# CPLD.net
KiCad netlist of a schematic drawn in Altium Designer
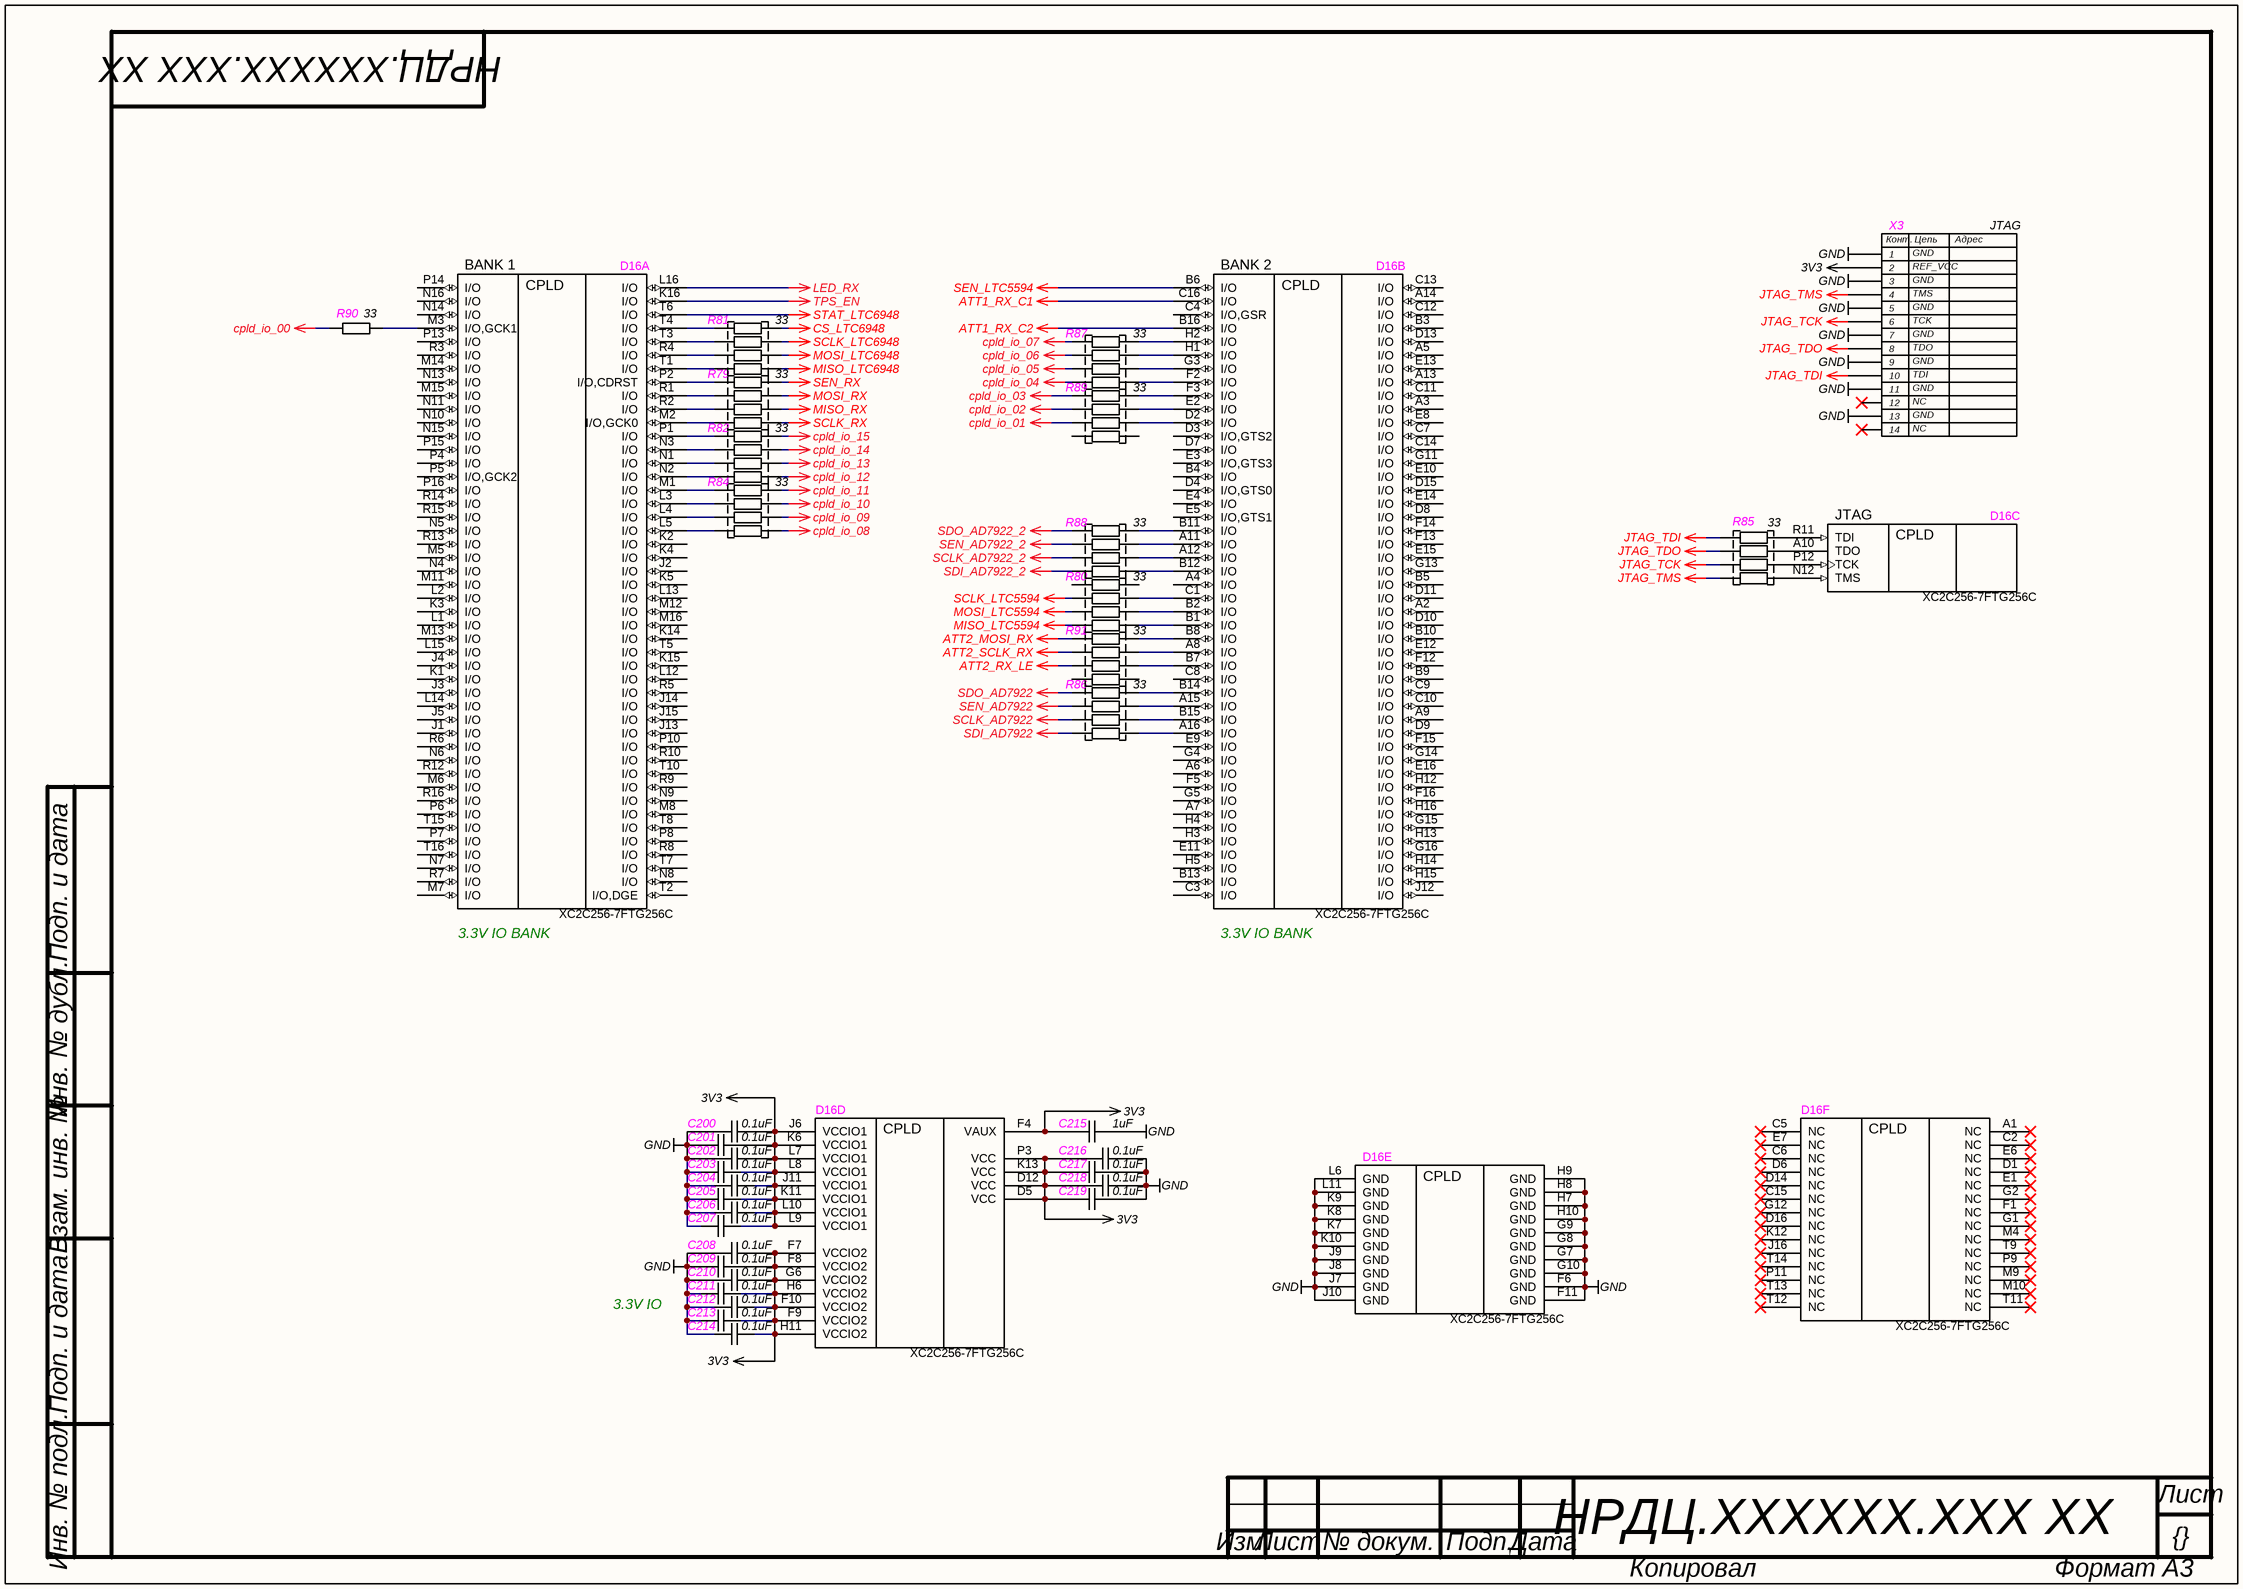
[diagram p0: CPLD.SchDoc]

(export (version "E")
  (design (tool "Eeschema 10.0.6"))
  (components
    (comp (ref "C200")
      (value "0.1uF")
      (footprint "C0402")
      (description "SMD Capacitor")
      (fields (field (name "MANUFACTURER") "Murata") (field (name "TOLERANCE") "10%"))
      (libsource (lib "Kintex_SDR") (part "CAP"))
    )
    (comp (ref "C201")
      (value "0.1uF")
      (footprint "C0402")
      (description "SMD Capacitor")
      (fields (field (name "MANUFACTURER") "Murata") (field (name "TOLERANCE") "10%"))
      (libsource (lib "Kintex_SDR") (part "CAP"))
    )
    (comp (ref "C202")
      (value "0.1uF")
      (footprint "C0402")
      (description "SMD Capacitor")
      (fields (field (name "MANUFACTURER") "Murata") (field (name "TOLERANCE") "10%"))
      (libsource (lib "Kintex_SDR") (part "CAP"))
    )
    (comp (ref "C203")
      (value "0.1uF")
      (footprint "C0402")
      (description "SMD Capacitor")
      (fields (field (name "MANUFACTURER") "Murata") (field (name "TOLERANCE") "10%"))
      (libsource (lib "Kintex_SDR") (part "CAP"))
    )
    (comp (ref "C204")
      (value "0.1uF")
      (footprint "C0402")
      (description "SMD Capacitor")
      (fields (field (name "MANUFACTURER") "Murata") (field (name "TOLERANCE") "10%"))
      (libsource (lib "Kintex_SDR") (part "CAP"))
    )
    (comp (ref "C205")
      (value "0.1uF")
      (footprint "C0402")
      (description "SMD Capacitor")
      (fields (field (name "MANUFACTURER") "Murata") (field (name "TOLERANCE") "10%"))
      (libsource (lib "Kintex_SDR") (part "CAP"))
    )
    (comp (ref "C206")
      (value "0.1uF")
      (footprint "C0402")
      (description "SMD Capacitor")
      (fields (field (name "MANUFACTURER") "Murata") (field (name "TOLERANCE") "10%"))
      (libsource (lib "Kintex_SDR") (part "CAP"))
    )
    (comp (ref "C207")
      (value "0.1uF")
      (footprint "C0402")
      (description "SMD Capacitor")
      (fields (field (name "MANUFACTURER") "Murata") (field (name "TOLERANCE") "10%"))
      (libsource (lib "Kintex_SDR") (part "CAP"))
    )
    (comp (ref "C208")
      (value "0.1uF")
      (footprint "C0402")
      (description "SMD Capacitor")
      (fields (field (name "MANUFACTURER") "Murata") (field (name "TOLERANCE") "10%"))
      (libsource (lib "Kintex_SDR") (part "CAP"))
    )
    (comp (ref "C209")
      (value "0.1uF")
      (footprint "C0402")
      (description "SMD Capacitor")
      (fields (field (name "MANUFACTURER") "Murata") (field (name "TOLERANCE") "10%"))
      (libsource (lib "Kintex_SDR") (part "CAP"))
    )
    (comp (ref "C210")
      (value "0.1uF")
      (footprint "C0402")
      (description "SMD Capacitor")
      (fields (field (name "MANUFACTURER") "Murata") (field (name "TOLERANCE") "10%"))
      (libsource (lib "Kintex_SDR") (part "CAP"))
    )
    (comp (ref "C211")
      (value "0.1uF")
      (footprint "C0402")
      (description "SMD Capacitor")
      (fields (field (name "MANUFACTURER") "Murata") (field (name "TOLERANCE") "10%"))
      (libsource (lib "Kintex_SDR") (part "CAP"))
    )
    (comp (ref "C212")
      (value "0.1uF")
      (footprint "C0402")
      (description "SMD Capacitor")
      (fields (field (name "MANUFACTURER") "Murata") (field (name "TOLERANCE") "10%"))
      (libsource (lib "Kintex_SDR") (part "CAP"))
    )
    (comp (ref "C213")
      (value "0.1uF")
      (footprint "C0402")
      (description "SMD Capacitor")
      (fields (field (name "MANUFACTURER") "Murata") (field (name "TOLERANCE") "10%"))
      (libsource (lib "Kintex_SDR") (part "CAP"))
    )
    (comp (ref "C214")
      (value "0.1uF")
      (footprint "C0402")
      (description "SMD Capacitor")
      (fields (field (name "MANUFACTURER") "Murata") (field (name "TOLERANCE") "10%"))
      (libsource (lib "Kintex_SDR") (part "CAP"))
    )
    (comp (ref "C215")
      (value "1uF")
      (footprint "C0402")
      (description "SMD Capacitor")
      (fields (field (name "MANUFACTURER") "Murata") (field (name "TOLERANCE") "10%"))
      (libsource (lib "Kintex_SDR") (part "CAP"))
    )
    (comp (ref "C216")
      (value "0.1uF")
      (footprint "C0402")
      (description "SMD Capacitor")
      (fields (field (name "MANUFACTURER") "Murata") (field (name "TOLERANCE") "10%"))
      (libsource (lib "Kintex_SDR") (part "CAP"))
    )
    (comp (ref "C217")
      (value "0.1uF")
      (footprint "C0402")
      (description "SMD Capacitor")
      (fields (field (name "MANUFACTURER") "Murata") (field (name "TOLERANCE") "10%"))
      (libsource (lib "Kintex_SDR") (part "CAP"))
    )
    (comp (ref "C218")
      (value "0.1uF")
      (footprint "C0402")
      (description "SMD Capacitor")
      (fields (field (name "MANUFACTURER") "Murata") (field (name "TOLERANCE") "10%"))
      (libsource (lib "Kintex_SDR") (part "CAP"))
    )
    (comp (ref "C219")
      (value "0.1uF")
      (footprint "C0402")
      (description "SMD Capacitor")
      (fields (field (name "MANUFACTURER") "Murata") (field (name "TOLERANCE") "10%"))
      (libsource (lib "Kintex_SDR") (part "CAP"))
    )
    (comp (ref "D16")
      (value "XC2C256-7FTG256C")
      (footprint "DBLib:FTG256")
      (description "CoolRunner-II 1.8V, 256 Macrocell CPLD, 184 User I/Os, 256-Ball FTBGA, Commercial Grade, Pb-Free")
      (libsource (lib "") (part "XC2C256-7FTG256C_2"))
    )
    (comp (ref "R79")
      (value "33")
      (footprint "EXN8V")
      (description "Chip Resistor Array")
      (fields (field (name "TOLERANCE") "5%") (field (name "MANUFACTURER") "Panasonic"))
      (libsource (lib "") (part "RES 4x0402_5"))
    )
    (comp (ref "R80")
      (value "33")
      (footprint "EXN8V")
      (description "Chip Resistor Array")
      (fields (field (name "TOLERANCE") "5%") (field (name "MANUFACTURER") "Panasonic"))
      (libsource (lib "Kintex_SDR") (part "RES 4x0402"))
    )
    (comp (ref "R81")
      (value "33")
      (footprint "EXN8V")
      (description "Chip Resistor Array")
      (fields (field (name "TOLERANCE") "5%") (field (name "MANUFACTURER") "Panasonic"))
      (libsource (lib "") (part "RES 4x0402_1"))
    )
    (comp (ref "R82")
      (value "33")
      (footprint "EXN8V")
      (description "Chip Resistor Array")
      (fields (field (name "TOLERANCE") "5%") (field (name "MANUFACTURER") "Panasonic"))
      (libsource (lib "") (part "RES 4x0402_3"))
    )
    (comp (ref "R84")
      (value "33")
      (footprint "EXN8V")
      (description "Chip Resistor Array")
      (fields (field (name "TOLERANCE") "5%") (field (name "MANUFACTURER") "Panasonic"))
      (libsource (lib "") (part "RES 4x0402_3"))
    )
    (comp (ref "R85")
      (value "33")
      (footprint "EXN8V")
      (description "Chip Resistor Array")
      (fields (field (name "TOLERANCE") "5%") (field (name "MANUFACTURER") "Panasonic"))
      (libsource (lib "Kintex_SDR") (part "RES 4x0402"))
    )
    (comp (ref "R86")
      (value "33")
      (footprint "EXN8V")
      (description "Chip Resistor Array")
      (fields (field (name "TOLERANCE") "5%") (field (name "MANUFACTURER") "Panasonic"))
      (libsource (lib "") (part "RES 4x0402_5"))
    )
    (comp (ref "R87")
      (value "33")
      (footprint "EXN8V")
      (description "Chip Resistor Array")
      (fields (field (name "TOLERANCE") "5%") (field (name "MANUFACTURER") "Panasonic"))
      (libsource (lib "Kintex_SDR") (part "RES 4x0402"))
    )
    (comp (ref "R88")
      (value "33")
      (footprint "EXN8V")
      (description "Chip Resistor Array")
      (fields (field (name "TOLERANCE") "5%") (field (name "MANUFACTURER") "Panasonic"))
      (libsource (lib "") (part "RES 4x0402_2"))
    )
    (comp (ref "R89")
      (value "33")
      (footprint "EXN8V")
      (description "Chip Resistor Array")
      (fields (field (name "TOLERANCE") "5%") (field (name "MANUFACTURER") "Panasonic"))
      (libsource (lib "Kintex_SDR") (part "RES 4x0402"))
    )
    (comp (ref "R90")
      (value "33")
      (footprint "R0402")
      (description "SMD Resistor")
      (fields (field (name "POWER") "0.1 Wt") (field (name "TOLERANCE") "1%"))
      (libsource (lib "Kintex_SDR") (part "RES"))
    )
    (comp (ref "R91")
      (value "33")
      (footprint "EXN8V")
      (description "Chip Resistor Array")
      (fields (field (name "TOLERANCE") "5%") (field (name "MANUFACTURER") "Panasonic"))
      (libsource (lib "") (part "RES 4x0402_4"))
    )
    (comp (ref "X3")
      (value "JTAG")
      (footprint "DBLib:JTAG Mail 2mm")
      (description "2.00mm Pitch, Milli-Grid PCB Header, Dual Row, Vertical, Through Hole, Shrouded, 14\r\nCircuits")
      (fields (field (name "MANUFACTURER") "Molex"))
      (libsource (lib "DBLib") (part "HDR Debug_14-pin"))
    )
  )
  (nets
    (net (code "1") (name "3V3") (class "Default")
      (node (ref "C200") (pin "2") (pinfunction "2_2") (pintype "passive"))
      (node (ref "C201") (pin "2") (pinfunction "2_2") (pintype "passive"))
      (node (ref "C202") (pin "2") (pinfunction "2_2") (pintype "passive"))
      (node (ref "C203") (pin "2") (pinfunction "2_2") (pintype "passive"))
      (node (ref "C204") (pin "2") (pinfunction "2_2") (pintype "passive"))
      (node (ref "C205") (pin "2") (pinfunction "2_2") (pintype "passive"))
      (node (ref "C206") (pin "2") (pinfunction "2_2") (pintype "passive"))
      (node (ref "C207") (pin "2") (pinfunction "2_2") (pintype "passive"))
      (node (ref "C208") (pin "2") (pinfunction "2_2") (pintype "passive"))
      (node (ref "C209") (pin "2") (pinfunction "2_2") (pintype "passive"))
      (node (ref "C210") (pin "2") (pinfunction "2_2") (pintype "passive"))
      (node (ref "C211") (pin "2") (pinfunction "2_2") (pintype "passive"))
      (node (ref "C212") (pin "2") (pinfunction "2_2") (pintype "passive"))
      (node (ref "C213") (pin "2") (pinfunction "2_2") (pintype "passive"))
      (node (ref "C214") (pin "2") (pinfunction "2_2") (pintype "passive"))
      (node (ref "C215") (pin "1") (pinfunction "1_1") (pintype "passive"))
      (node (ref "C216") (pin "1") (pinfunction "1_1") (pintype "passive"))
      (node (ref "C217") (pin "1") (pinfunction "1_1") (pintype "passive"))
      (node (ref "C218") (pin "1") (pinfunction "1_1") (pintype "passive"))
      (node (ref "C219") (pin "1") (pinfunction "1_1") (pintype "passive"))
      (node (ref "D16") (pin "D12") (pinfunction "VCC_D12") (pintype "power_in"))
      (node (ref "D16") (pin "D5") (pinfunction "VCC_D5") (pintype "power_in"))
      (node (ref "D16") (pin "F10") (pinfunction "VCCIO2_F10") (pintype "power_in"))
      (node (ref "D16") (pin "F4") (pinfunction "VAUX_F4") (pintype "power_in"))
      (node (ref "D16") (pin "F7") (pinfunction "VCCIO2_F7") (pintype "power_in"))
      (node (ref "D16") (pin "F8") (pinfunction "VCCIO2_F8") (pintype "power_in"))
      (node (ref "D16") (pin "F9") (pinfunction "VCCIO2_F9") (pintype "power_in"))
      (node (ref "D16") (pin "G6") (pinfunction "VCCIO2_G6") (pintype "power_in"))
      (node (ref "D16") (pin "H11") (pinfunction "VCCIO2_H11") (pintype "power_in"))
      (node (ref "D16") (pin "H6") (pinfunction "VCCIO2_H6") (pintype "power_in"))
      (node (ref "D16") (pin "J11") (pinfunction "VCCIO1_J11") (pintype "power_in"))
      (node (ref "D16") (pin "J6") (pinfunction "VCCIO1_J6") (pintype "power_in"))
      (node (ref "D16") (pin "K11") (pinfunction "VCCIO1_K11") (pintype "power_in"))
      (node (ref "D16") (pin "K13") (pinfunction "VCC_K13") (pintype "power_in"))
      (node (ref "D16") (pin "K6") (pinfunction "VCCIO1_K6") (pintype "power_in"))
      (node (ref "D16") (pin "L10") (pinfunction "VCCIO1_L10") (pintype "power_in"))
      (node (ref "D16") (pin "L7") (pinfunction "VCCIO1_L7") (pintype "power_in"))
      (node (ref "D16") (pin "L8") (pinfunction "VCCIO1_L8") (pintype "power_in"))
      (node (ref "D16") (pin "L9") (pinfunction "VCCIO1_L9") (pintype "power_in"))
      (node (ref "D16") (pin "P3") (pinfunction "VCC_P3") (pintype "power_in"))
      (node (ref "X3") (pin "2") (pinfunction "2_2") (pintype "passive"))
    )
    (net (code "2") (name "ATT1_RX_C1") (class "Default")
      (node (ref "D16") (pin "C16") (pinfunction "I/O_C16") (pintype "bidirectional"))
    )
    (net (code "3") (name "ATT1_RX_C2") (class "Default")
      (node (ref "D16") (pin "B16") (pinfunction "I/O_B16") (pintype "bidirectional"))
    )
    (net (code "4") (name "ATT2_MOSI_RX") (class "Default")
      (node (ref "R91") (pin "5") (pinfunction "5_5") (pintype "passive"))
    )
    (net (code "5") (name "ATT2_RX_LE") (class "Default")
      (node (ref "R91") (pin "7") (pinfunction "7_7") (pintype "passive"))
    )
    (net (code "6") (name "ATT2_SCLK_RX") (class "Default")
      (node (ref "R91") (pin "6") (pinfunction "6_6") (pintype "passive"))
    )
    (net (code "7") (name "CS_LTC6948") (class "Default")
      (node (ref "R81") (pin "8") (pinfunction "8_8") (pintype "passive"))
    )
    (net (code "8") (name "GND") (class "Default")
      (node (ref "C200") (pin "1") (pinfunction "1_1") (pintype "passive"))
      (node (ref "C201") (pin "1") (pinfunction "1_1") (pintype "passive"))
      (node (ref "C202") (pin "1") (pinfunction "1_1") (pintype "passive"))
      (node (ref "C203") (pin "1") (pinfunction "1_1") (pintype "passive"))
      (node (ref "C204") (pin "1") (pinfunction "1_1") (pintype "passive"))
      (node (ref "C205") (pin "1") (pinfunction "1_1") (pintype "passive"))
      (node (ref "C206") (pin "1") (pinfunction "1_1") (pintype "passive"))
      (node (ref "C207") (pin "1") (pinfunction "1_1") (pintype "passive"))
      (node (ref "C208") (pin "1") (pinfunction "1_1") (pintype "passive"))
      (node (ref "C209") (pin "1") (pinfunction "1_1") (pintype "passive"))
      (node (ref "C210") (pin "1") (pinfunction "1_1") (pintype "passive"))
      (node (ref "C211") (pin "1") (pinfunction "1_1") (pintype "passive"))
      (node (ref "C212") (pin "1") (pinfunction "1_1") (pintype "passive"))
      (node (ref "C213") (pin "1") (pinfunction "1_1") (pintype "passive"))
      (node (ref "C214") (pin "1") (pinfunction "1_1") (pintype "passive"))
      (node (ref "C215") (pin "2") (pinfunction "2_2") (pintype "passive"))
      (node (ref "C216") (pin "2") (pinfunction "2_2") (pintype "passive"))
      (node (ref "C217") (pin "2") (pinfunction "2_2") (pintype "passive"))
      (node (ref "C218") (pin "2") (pinfunction "2_2") (pintype "passive"))
      (node (ref "C219") (pin "2") (pinfunction "2_2") (pintype "passive"))
      (node (ref "D16") (pin "F11") (pinfunction "GND_F11") (pintype "power_in"))
      (node (ref "D16") (pin "F6") (pinfunction "GND_F6") (pintype "power_in"))
      (node (ref "D16") (pin "G10") (pinfunction "GND_G10") (pintype "power_in"))
      (node (ref "D16") (pin "G7") (pinfunction "GND_G7") (pintype "power_in"))
      (node (ref "D16") (pin "G8") (pinfunction "GND_G8") (pintype "power_in"))
      (node (ref "D16") (pin "G9") (pinfunction "GND_G9") (pintype "power_in"))
      (node (ref "D16") (pin "H10") (pinfunction "GND_H10") (pintype "power_in"))
      (node (ref "D16") (pin "H7") (pinfunction "GND_H7") (pintype "power_in"))
      (node (ref "D16") (pin "H8") (pinfunction "GND_H8") (pintype "power_in"))
      (node (ref "D16") (pin "H9") (pinfunction "GND_H9") (pintype "power_in"))
      (node (ref "D16") (pin "J10") (pinfunction "GND_J10") (pintype "power_in"))
      (node (ref "D16") (pin "J7") (pinfunction "GND_J7") (pintype "power_in"))
      (node (ref "D16") (pin "J8") (pinfunction "GND_J8") (pintype "power_in"))
      (node (ref "D16") (pin "J9") (pinfunction "GND_J9") (pintype "power_in"))
      (node (ref "D16") (pin "K10") (pinfunction "GND_K10") (pintype "power_in"))
      (node (ref "D16") (pin "K7") (pinfunction "GND_K7") (pintype "power_in"))
      (node (ref "D16") (pin "K8") (pinfunction "GND_K8") (pintype "power_in"))
      (node (ref "D16") (pin "K9") (pinfunction "GND_K9") (pintype "power_in"))
      (node (ref "D16") (pin "L11") (pinfunction "GND_L11") (pintype "power_in"))
      (node (ref "D16") (pin "L6") (pinfunction "GND_L6") (pintype "power_in"))
      (node (ref "X3") (pin "1") (pinfunction "1_1") (pintype "passive"))
      (node (ref "X3") (pin "11") (pinfunction "11_11") (pintype "passive"))
      (node (ref "X3") (pin "13") (pinfunction "13_13") (pintype "passive"))
      (node (ref "X3") (pin "3") (pinfunction "3_3") (pintype "passive"))
      (node (ref "X3") (pin "5") (pinfunction "5_5") (pintype "passive"))
      (node (ref "X3") (pin "7") (pinfunction "7_7") (pintype "passive"))
      (node (ref "X3") (pin "9") (pinfunction "9_9") (pintype "passive"))
    )
    (net (code "9") (name "JTAG_TCK") (class "Default")
      (node (ref "R85") (pin "6") (pinfunction "6_6") (pintype "passive"))
      (node (ref "X3") (pin "6") (pinfunction "6_6") (pintype "passive"))
    )
    (net (code "10") (name "JTAG_TDI") (class "Default")
      (node (ref "R85") (pin "8") (pinfunction "8_8") (pintype "passive"))
      (node (ref "X3") (pin "10") (pinfunction "10_10") (pintype "passive"))
    )
    (net (code "11") (name "JTAG_TDO") (class "Default")
      (node (ref "R85") (pin "7") (pinfunction "7_7") (pintype "passive"))
      (node (ref "X3") (pin "8") (pinfunction "8_8") (pintype "passive"))
    )
    (net (code "12") (name "JTAG_TMS") (class "Default")
      (node (ref "R85") (pin "5") (pinfunction "5_5") (pintype "passive"))
      (node (ref "X3") (pin "4") (pinfunction "4_4") (pintype "passive"))
    )
    (net (code "13") (name "LED_RX") (class "Default")
      (node (ref "D16") (pin "L16") (pinfunction "I/O_L16") (pintype "bidirectional"))
    )
    (net (code "14") (name "MISO_LTC5594") (class "Default")
      (node (ref "R80") (pin "5") (pinfunction "5_5") (pintype "passive"))
    )
    (net (code "15") (name "MISO_LTC6948") (class "Default")
      (node (ref "R81") (pin "5") (pinfunction "5_5") (pintype "passive"))
    )
    (net (code "16") (name "MISO_RX") (class "Default")
      (node (ref "R79") (pin "7") (pinfunction "7_7") (pintype "passive"))
    )
    (net (code "17") (name "MOSI_LTC5594") (class "Default")
      (node (ref "R80") (pin "6") (pinfunction "6_6") (pintype "passive"))
    )
    (net (code "18") (name "MOSI_LTC6948") (class "Default")
      (node (ref "R81") (pin "6") (pinfunction "6_6") (pintype "passive"))
    )
    (net (code "19") (name "MOSI_RX") (class "Default")
      (node (ref "R79") (pin "6") (pinfunction "6_6") (pintype "passive"))
    )
    (net (code "20") (name "Net-(D16A-I{slash}O,CDRST)") (class "Default")
      (node (ref "D16") (pin "P2") (pinfunction "I/O,CDRST_P2") (pintype "bidirectional"))
      (node (ref "R79") (pin "4") (pinfunction "4_4") (pintype "passive"))
    )
    (net (code "21") (name "Net-(D16A-I{slash}O,GCK0)") (class "Default")
      (node (ref "D16") (pin "M2") (pinfunction "I/O,GCK0_M2") (pintype "bidirectional"))
      (node (ref "R79") (pin "1") (pinfunction "1_1") (pintype "passive"))
    )
    (net (code "22") (name "Net-(D16A-I{slash}O,GCK1)") (class "Default")
      (node (ref "D16") (pin "M3") (pinfunction "I/O,GCK1_M3") (pintype "bidirectional"))
      (node (ref "R90") (pin "1") (pinfunction "1_1") (pintype "passive"))
    )
    (net (code "23") (name "Net-(D16A-I{slash}O-PadL3)") (class "Default")
      (node (ref "D16") (pin "L3") (pinfunction "I/O_L3") (pintype "bidirectional"))
      (node (ref "R84") (pin "2") (pinfunction "2_2") (pintype "passive"))
    )
    (net (code "24") (name "Net-(D16A-I{slash}O-PadL4)") (class "Default")
      (node (ref "D16") (pin "L4") (pinfunction "I/O_L4") (pintype "bidirectional"))
      (node (ref "R84") (pin "3") (pinfunction "3_3") (pintype "passive"))
    )
    (net (code "25") (name "Net-(D16A-I{slash}O-PadL5)") (class "Default")
      (node (ref "D16") (pin "L5") (pinfunction "I/O_L5") (pintype "bidirectional"))
      (node (ref "R84") (pin "4") (pinfunction "4_4") (pintype "passive"))
    )
    (net (code "26") (name "Net-(D16A-I{slash}O-PadM1)") (class "Default")
      (node (ref "D16") (pin "M1") (pinfunction "I/O_M1") (pintype "bidirectional"))
      (node (ref "R84") (pin "1") (pinfunction "1_1") (pintype "passive"))
    )
    (net (code "27") (name "Net-(D16A-I{slash}O-PadN1)") (class "Default")
      (node (ref "D16") (pin "N1") (pinfunction "I/O_N1") (pintype "bidirectional"))
      (node (ref "R82") (pin "3") (pinfunction "3_3") (pintype "passive"))
    )
    (net (code "28") (name "Net-(D16A-I{slash}O-PadN2)") (class "Default")
      (node (ref "D16") (pin "N2") (pinfunction "I/O_N2") (pintype "bidirectional"))
      (node (ref "R82") (pin "4") (pinfunction "4_4") (pintype "passive"))
    )
    (net (code "29") (name "Net-(D16A-I{slash}O-PadN3)") (class "Default")
      (node (ref "D16") (pin "N3") (pinfunction "I/O_N3") (pintype "bidirectional"))
      (node (ref "R82") (pin "2") (pinfunction "2_2") (pintype "passive"))
    )
    (net (code "30") (name "Net-(D16A-I{slash}O-PadP1)") (class "Default")
      (node (ref "D16") (pin "P1") (pinfunction "I/O_P1") (pintype "bidirectional"))
      (node (ref "R82") (pin "1") (pinfunction "1_1") (pintype "passive"))
    )
    (net (code "31") (name "Net-(D16A-I{slash}O-PadR1)") (class "Default")
      (node (ref "D16") (pin "R1") (pinfunction "I/O_R1") (pintype "bidirectional"))
      (node (ref "R79") (pin "3") (pinfunction "3_3") (pintype "passive"))
    )
    (net (code "32") (name "Net-(D16A-I{slash}O-PadR2)") (class "Default")
      (node (ref "D16") (pin "R2") (pinfunction "I/O_R2") (pintype "bidirectional"))
      (node (ref "R79") (pin "2") (pinfunction "2_2") (pintype "passive"))
    )
    (net (code "33") (name "Net-(D16A-I{slash}O-PadR4)") (class "Default")
      (node (ref "D16") (pin "R4") (pinfunction "I/O_R4") (pintype "bidirectional"))
      (node (ref "R81") (pin "2") (pinfunction "2_2") (pintype "passive"))
    )
    (net (code "34") (name "Net-(D16A-I{slash}O-PadT1)") (class "Default")
      (node (ref "D16") (pin "T1") (pinfunction "I/O_T1") (pintype "bidirectional"))
      (node (ref "R81") (pin "4") (pinfunction "4_4") (pintype "passive"))
    )
    (net (code "35") (name "Net-(D16A-I{slash}O-PadT3)") (class "Default")
      (node (ref "D16") (pin "T3") (pinfunction "I/O_T3") (pintype "bidirectional"))
      (node (ref "R81") (pin "3") (pinfunction "3_3") (pintype "passive"))
    )
    (net (code "36") (name "Net-(D16A-I{slash}O-PadT4)") (class "Default")
      (node (ref "D16") (pin "T4") (pinfunction "I/O_T4") (pintype "bidirectional"))
      (node (ref "R81") (pin "1") (pinfunction "1_1") (pintype "passive"))
    )
    (net (code "37") (name "Net-(D16B-I{slash}O-PadA8)") (class "Default")
      (node (ref "D16") (pin "A8") (pinfunction "I/O_A8") (pintype "bidirectional"))
      (node (ref "R91") (pin "3") (pinfunction "3_3") (pintype "passive"))
    )
    (net (code "38") (name "Net-(D16B-I{slash}O-PadA11)") (class "Default")
      (node (ref "D16") (pin "A11") (pinfunction "I/O_A11") (pintype "bidirectional"))
      (node (ref "R88") (pin "1") (pinfunction "1_1") (pintype "passive"))
    )
    (net (code "39") (name "Net-(D16B-I{slash}O-PadA12)") (class "Default")
      (node (ref "D16") (pin "A12") (pinfunction "I/O_A12") (pintype "bidirectional"))
      (node (ref "R88") (pin "3") (pinfunction "3_3") (pintype "passive"))
    )
    (net (code "40") (name "Net-(D16B-I{slash}O-PadA15)") (class "Default")
      (node (ref "D16") (pin "A15") (pinfunction "I/O_A15") (pintype "bidirectional"))
      (node (ref "R86") (pin "6") (pinfunction "6_6") (pintype "passive"))
    )
    (net (code "41") (name "Net-(D16B-I{slash}O-PadA16)") (class "Default")
      (node (ref "D16") (pin "A16") (pinfunction "I/O_A16") (pintype "bidirectional"))
      (node (ref "R86") (pin "8") (pinfunction "8_8") (pintype "passive"))
    )
    (net (code "42") (name "Net-(D16B-I{slash}O-PadB1)") (class "Default")
      (node (ref "D16") (pin "B1") (pinfunction "I/O_B1") (pintype "bidirectional"))
      (node (ref "R80") (pin "4") (pinfunction "4_4") (pintype "passive"))
    )
    (net (code "43") (name "Net-(D16B-I{slash}O-PadB2)") (class "Default")
      (node (ref "D16") (pin "B2") (pinfunction "I/O_B2") (pintype "bidirectional"))
      (node (ref "R80") (pin "3") (pinfunction "3_3") (pintype "passive"))
    )
    (net (code "44") (name "Net-(D16B-I{slash}O-PadB7)") (class "Default")
      (node (ref "D16") (pin "B7") (pinfunction "I/O_B7") (pintype "bidirectional"))
      (node (ref "R91") (pin "2") (pinfunction "2_2") (pintype "passive"))
    )
    (net (code "45") (name "Net-(D16B-I{slash}O-PadB8)") (class "Default")
      (node (ref "D16") (pin "B8") (pinfunction "I/O_B8") (pintype "bidirectional"))
      (node (ref "R91") (pin "4") (pinfunction "4_4") (pintype "passive"))
    )
    (net (code "46") (name "Net-(D16B-I{slash}O-PadB11)") (class "Default")
      (node (ref "D16") (pin "B11") (pinfunction "I/O_B11") (pintype "bidirectional"))
      (node (ref "R88") (pin "2") (pinfunction "2_2") (pintype "passive"))
    )
    (net (code "47") (name "Net-(D16B-I{slash}O-PadB12)") (class "Default")
      (node (ref "D16") (pin "B12") (pinfunction "I/O_B12") (pintype "bidirectional"))
      (node (ref "R88") (pin "4") (pinfunction "4_4") (pintype "passive"))
    )
    (net (code "48") (name "Net-(D16B-I{slash}O-PadB14)") (class "Default")
      (node (ref "D16") (pin "B14") (pinfunction "I/O_B14") (pintype "bidirectional"))
      (node (ref "R86") (pin "5") (pinfunction "5_5") (pintype "passive"))
    )
    (net (code "49") (name "Net-(D16B-I{slash}O-PadB15)") (class "Default")
      (node (ref "D16") (pin "B15") (pinfunction "I/O_B15") (pintype "bidirectional"))
      (node (ref "R86") (pin "7") (pinfunction "7_7") (pintype "passive"))
    )
    (net (code "50") (name "Net-(D16B-I{slash}O-PadC1)") (class "Default")
      (node (ref "D16") (pin "C1") (pinfunction "I/O_C1") (pintype "bidirectional"))
      (node (ref "R80") (pin "2") (pinfunction "2_2") (pintype "passive"))
    )
    (net (code "51") (name "Net-(D16B-I{slash}O-PadD2)") (class "Default")
      (node (ref "D16") (pin "D2") (pinfunction "I/O_D2") (pintype "bidirectional"))
      (node (ref "R89") (pin "3") (pinfunction "3_3") (pintype "passive"))
    )
    (net (code "52") (name "Net-(D16B-I{slash}O-PadE2)") (class "Default")
      (node (ref "D16") (pin "E2") (pinfunction "I/O_E2") (pintype "bidirectional"))
      (node (ref "R89") (pin "2") (pinfunction "2_2") (pintype "passive"))
    )
    (net (code "53") (name "Net-(D16B-I{slash}O-PadF2)") (class "Default")
      (node (ref "D16") (pin "F2") (pinfunction "I/O_F2") (pintype "bidirectional"))
      (node (ref "R87") (pin "4") (pinfunction "4_4") (pintype "passive"))
    )
    (net (code "54") (name "Net-(D16B-I{slash}O-PadF3)") (class "Default")
      (node (ref "D16") (pin "F3") (pinfunction "I/O_F3") (pintype "bidirectional"))
      (node (ref "R89") (pin "1") (pinfunction "1_1") (pintype "passive"))
    )
    (net (code "55") (name "Net-(D16B-I{slash}O-PadG3)") (class "Default")
      (node (ref "D16") (pin "G3") (pinfunction "I/O_G3") (pintype "bidirectional"))
      (node (ref "R87") (pin "3") (pinfunction "3_3") (pintype "passive"))
    )
    (net (code "56") (name "Net-(D16B-I{slash}O-PadH1)") (class "Default")
      (node (ref "D16") (pin "H1") (pinfunction "I/O_H1") (pintype "bidirectional"))
      (node (ref "R87") (pin "2") (pinfunction "2_2") (pintype "passive"))
    )
    (net (code "57") (name "Net-(D16B-I{slash}O-PadH2)") (class "Default")
      (node (ref "D16") (pin "H2") (pinfunction "I/O_H2") (pintype "bidirectional"))
      (node (ref "R87") (pin "1") (pinfunction "1_1") (pintype "passive"))
    )
    (net (code "58") (name "Net-(D16C-TCK)") (class "Default")
      (node (ref "D16") (pin "P12") (pinfunction "TCK_P12") (pintype "input"))
      (node (ref "R85") (pin "3") (pinfunction "3_3") (pintype "passive"))
    )
    (net (code "59") (name "Net-(D16C-TDI)") (class "Default")
      (node (ref "D16") (pin "R11") (pinfunction "TDI_R11") (pintype "input"))
      (node (ref "R85") (pin "1") (pinfunction "1_1") (pintype "passive"))
    )
    (net (code "60") (name "Net-(D16C-TDO)") (class "Default")
      (node (ref "D16") (pin "A10") (pinfunction "TDO_A10") (pintype "passive"))
      (node (ref "R85") (pin "2") (pinfunction "2_2") (pintype "passive"))
    )
    (net (code "61") (name "Net-(D16C-TMS)") (class "Default")
      (node (ref "D16") (pin "N12") (pinfunction "TMS_N12") (pintype "input"))
      (node (ref "R85") (pin "4") (pinfunction "4_4") (pintype "passive"))
    )
    (net (code "62") (name "SCLK_AD7922") (class "Default")
      (node (ref "R86") (pin "2") (pinfunction "2_2") (pintype "passive"))
    )
    (net (code "63") (name "SCLK_AD7922_2") (class "Default")
      (node (ref "R88") (pin "6") (pinfunction "6_6") (pintype "passive"))
    )
    (net (code "64") (name "SCLK_LTC5594") (class "Default")
      (node (ref "R80") (pin "7") (pinfunction "7_7") (pintype "passive"))
    )
    (net (code "65") (name "SCLK_LTC6948") (class "Default")
      (node (ref "R81") (pin "7") (pinfunction "7_7") (pintype "passive"))
    )
    (net (code "66") (name "SCLK_RX") (class "Default")
      (node (ref "R79") (pin "8") (pinfunction "8_8") (pintype "passive"))
    )
    (net (code "67") (name "SDI_AD7922") (class "Default")
      (node (ref "R86") (pin "1") (pinfunction "1_1") (pintype "passive"))
    )
    (net (code "68") (name "SDI_AD7922_2") (class "Default")
      (node (ref "R88") (pin "5") (pinfunction "5_5") (pintype "passive"))
    )
    (net (code "69") (name "SDO_AD7922") (class "Default")
      (node (ref "R86") (pin "4") (pinfunction "4_4") (pintype "passive"))
    )
    (net (code "70") (name "SDO_AD7922_2") (class "Default")
      (node (ref "R88") (pin "8") (pinfunction "8_8") (pintype "passive"))
    )
    (net (code "71") (name "SEN_AD7922") (class "Default")
      (node (ref "R86") (pin "3") (pinfunction "3_3") (pintype "passive"))
    )
    (net (code "72") (name "SEN_AD7922_2") (class "Default")
      (node (ref "R88") (pin "7") (pinfunction "7_7") (pintype "passive"))
    )
    (net (code "73") (name "SEN_LTC5594") (class "Default")
      (node (ref "D16") (pin "B6") (pinfunction "I/O_B6") (pintype "bidirectional"))
    )
    (net (code "74") (name "SEN_RX") (class "Default")
      (node (ref "R79") (pin "5") (pinfunction "5_5") (pintype "passive"))
    )
    (net (code "75") (name "STAT_LTC6948") (class "Default")
      (node (ref "D16") (pin "T6") (pinfunction "I/O_T6") (pintype "bidirectional"))
    )
    (net (code "76") (name "TPS_EN") (class "Default")
      (node (ref "D16") (pin "K16") (pinfunction "I/O_K16") (pintype "bidirectional"))
    )
    (net (code "77") (name "cpld_io_00") (class "Default")
      (node (ref "R90") (pin "2") (pinfunction "2_2") (pintype "passive"))
    )
    (net (code "78") (name "cpld_io_01") (class "Default")
      (node (ref "R89") (pin "6") (pinfunction "6_6") (pintype "passive"))
    )
    (net (code "79") (name "cpld_io_02") (class "Default")
      (node (ref "R89") (pin "7") (pinfunction "7_7") (pintype "passive"))
    )
    (net (code "80") (name "cpld_io_03") (class "Default")
      (node (ref "R89") (pin "8") (pinfunction "8_8") (pintype "passive"))
    )
    (net (code "81") (name "cpld_io_04") (class "Default")
      (node (ref "R87") (pin "5") (pinfunction "5_5") (pintype "passive"))
    )
    (net (code "82") (name "cpld_io_05") (class "Default")
      (node (ref "R87") (pin "6") (pinfunction "6_6") (pintype "passive"))
    )
    (net (code "83") (name "cpld_io_06") (class "Default")
      (node (ref "R87") (pin "7") (pinfunction "7_7") (pintype "passive"))
    )
    (net (code "84") (name "cpld_io_07") (class "Default")
      (node (ref "R87") (pin "8") (pinfunction "8_8") (pintype "passive"))
    )
    (net (code "85") (name "cpld_io_08") (class "Default")
      (node (ref "R84") (pin "5") (pinfunction "5_5") (pintype "passive"))
    )
    (net (code "86") (name "cpld_io_09") (class "Default")
      (node (ref "R84") (pin "6") (pinfunction "6_6") (pintype "passive"))
    )
    (net (code "87") (name "cpld_io_10") (class "Default")
      (node (ref "R84") (pin "7") (pinfunction "7_7") (pintype "passive"))
    )
    (net (code "88") (name "cpld_io_11") (class "Default")
      (node (ref "R84") (pin "8") (pinfunction "8_8") (pintype "passive"))
    )
    (net (code "89") (name "cpld_io_12") (class "Default")
      (node (ref "R82") (pin "5") (pinfunction "5_5") (pintype "passive"))
    )
    (net (code "90") (name "cpld_io_13") (class "Default")
      (node (ref "R82") (pin "6") (pinfunction "6_6") (pintype "passive"))
    )
    (net (code "91") (name "cpld_io_14") (class "Default")
      (node (ref "R82") (pin "7") (pinfunction "7_7") (pintype "passive"))
    )
    (net (code "92") (name "cpld_io_15") (class "Default")
      (node (ref "R82") (pin "8") (pinfunction "8_8") (pintype "passive"))
    )
    (net (code "93") (name "unconnected-(D16A-I{slash}O,DGE-PadT2)") (class "Default")
      (node (ref "D16") (pin "T2") (pinfunction "I/O,DGE_T2") (pintype "bidirectional"))
    )
    (net (code "94") (name "unconnected-(D16A-I{slash}O,GCK2-PadP5)") (class "Default")
      (node (ref "D16") (pin "P5") (pinfunction "I/O,GCK2_P5") (pintype "bidirectional"))
    )
    (net (code "95") (name "unconnected-(D16A-I{slash}O-PadJ1)") (class "Default")
      (node (ref "D16") (pin "J1") (pinfunction "I/O_J1") (pintype "bidirectional"))
    )
    (net (code "96") (name "unconnected-(D16A-I{slash}O-PadJ2)") (class "Default")
      (node (ref "D16") (pin "J2") (pinfunction "I/O_J2") (pintype "bidirectional"))
    )
    (net (code "97") (name "unconnected-(D16A-I{slash}O-PadJ3)") (class "Default")
      (node (ref "D16") (pin "J3") (pinfunction "I/O_J3") (pintype "bidirectional"))
    )
    (net (code "98") (name "unconnected-(D16A-I{slash}O-PadJ4)") (class "Default")
      (node (ref "D16") (pin "J4") (pinfunction "I/O_J4") (pintype "bidirectional"))
    )
    (net (code "99") (name "unconnected-(D16A-I{slash}O-PadJ5)") (class "Default")
      (node (ref "D16") (pin "J5") (pinfunction "I/O_J5") (pintype "bidirectional"))
    )
    (net (code "100") (name "unconnected-(D16A-I{slash}O-PadJ13)") (class "Default")
      (node (ref "D16") (pin "J13") (pinfunction "I/O_J13") (pintype "bidirectional"))
    )
    (net (code "101") (name "unconnected-(D16A-I{slash}O-PadJ14)") (class "Default")
      (node (ref "D16") (pin "J14") (pinfunction "I/O_J14") (pintype "bidirectional"))
    )
    (net (code "102") (name "unconnected-(D16A-I{slash}O-PadJ15)") (class "Default")
      (node (ref "D16") (pin "J15") (pinfunction "I/O_J15") (pintype "bidirectional"))
    )
    (net (code "103") (name "unconnected-(D16A-I{slash}O-PadK1)") (class "Default")
      (node (ref "D16") (pin "K1") (pinfunction "I/O_K1") (pintype "bidirectional"))
    )
    (net (code "104") (name "unconnected-(D16A-I{slash}O-PadK2)") (class "Default")
      (node (ref "D16") (pin "K2") (pinfunction "I/O_K2") (pintype "bidirectional"))
    )
    (net (code "105") (name "unconnected-(D16A-I{slash}O-PadK3)") (class "Default")
      (node (ref "D16") (pin "K3") (pinfunction "I/O_K3") (pintype "bidirectional"))
    )
    (net (code "106") (name "unconnected-(D16A-I{slash}O-PadK4)") (class "Default")
      (node (ref "D16") (pin "K4") (pinfunction "I/O_K4") (pintype "bidirectional"))
    )
    (net (code "107") (name "unconnected-(D16A-I{slash}O-PadK5)") (class "Default")
      (node (ref "D16") (pin "K5") (pinfunction "I/O_K5") (pintype "bidirectional"))
    )
    (net (code "108") (name "unconnected-(D16A-I{slash}O-PadK14)") (class "Default")
      (node (ref "D16") (pin "K14") (pinfunction "I/O_K14") (pintype "bidirectional"))
    )
    (net (code "109") (name "unconnected-(D16A-I{slash}O-PadK15)") (class "Default")
      (node (ref "D16") (pin "K15") (pinfunction "I/O_K15") (pintype "bidirectional"))
    )
    (net (code "110") (name "unconnected-(D16A-I{slash}O-PadL1)") (class "Default")
      (node (ref "D16") (pin "L1") (pinfunction "I/O_L1") (pintype "bidirectional"))
    )
    (net (code "111") (name "unconnected-(D16A-I{slash}O-PadL2)") (class "Default")
      (node (ref "D16") (pin "L2") (pinfunction "I/O_L2") (pintype "bidirectional"))
    )
    (net (code "112") (name "unconnected-(D16A-I{slash}O-PadL12)") (class "Default")
      (node (ref "D16") (pin "L12") (pinfunction "I/O_L12") (pintype "bidirectional"))
    )
    (net (code "113") (name "unconnected-(D16A-I{slash}O-PadL13)") (class "Default")
      (node (ref "D16") (pin "L13") (pinfunction "I/O_L13") (pintype "bidirectional"))
    )
    (net (code "114") (name "unconnected-(D16A-I{slash}O-PadL14)") (class "Default")
      (node (ref "D16") (pin "L14") (pinfunction "I/O_L14") (pintype "bidirectional"))
    )
    (net (code "115") (name "unconnected-(D16A-I{slash}O-PadL15)") (class "Default")
      (node (ref "D16") (pin "L15") (pinfunction "I/O_L15") (pintype "bidirectional"))
    )
    (net (code "116") (name "unconnected-(D16A-I{slash}O-PadM5)") (class "Default")
      (node (ref "D16") (pin "M5") (pinfunction "I/O_M5") (pintype "bidirectional"))
    )
    (net (code "117") (name "unconnected-(D16A-I{slash}O-PadM6)") (class "Default")
      (node (ref "D16") (pin "M6") (pinfunction "I/O_M6") (pintype "bidirectional"))
    )
    (net (code "118") (name "unconnected-(D16A-I{slash}O-PadM7)") (class "Default")
      (node (ref "D16") (pin "M7") (pinfunction "I/O_M7") (pintype "bidirectional"))
    )
    (net (code "119") (name "unconnected-(D16A-I{slash}O-PadM8)") (class "Default")
      (node (ref "D16") (pin "M8") (pinfunction "I/O_M8") (pintype "bidirectional"))
    )
    (net (code "120") (name "unconnected-(D16A-I{slash}O-PadM11)") (class "Default")
      (node (ref "D16") (pin "M11") (pinfunction "I/O_M11") (pintype "bidirectional"))
    )
    (net (code "121") (name "unconnected-(D16A-I{slash}O-PadM12)") (class "Default")
      (node (ref "D16") (pin "M12") (pinfunction "I/O_M12") (pintype "bidirectional"))
    )
    (net (code "122") (name "unconnected-(D16A-I{slash}O-PadM13)") (class "Default")
      (node (ref "D16") (pin "M13") (pinfunction "I/O_M13") (pintype "bidirectional"))
    )
    (net (code "123") (name "unconnected-(D16A-I{slash}O-PadM14)") (class "Default")
      (node (ref "D16") (pin "M14") (pinfunction "I/O_M14") (pintype "bidirectional"))
    )
    (net (code "124") (name "unconnected-(D16A-I{slash}O-PadM15)") (class "Default")
      (node (ref "D16") (pin "M15") (pinfunction "I/O_M15") (pintype "bidirectional"))
    )
    (net (code "125") (name "unconnected-(D16A-I{slash}O-PadM16)") (class "Default")
      (node (ref "D16") (pin "M16") (pinfunction "I/O_M16") (pintype "bidirectional"))
    )
    (net (code "126") (name "unconnected-(D16A-I{slash}O-PadN4)") (class "Default")
      (node (ref "D16") (pin "N4") (pinfunction "I/O_N4") (pintype "bidirectional"))
    )
    (net (code "127") (name "unconnected-(D16A-I{slash}O-PadN5)") (class "Default")
      (node (ref "D16") (pin "N5") (pinfunction "I/O_N5") (pintype "bidirectional"))
    )
    (net (code "128") (name "unconnected-(D16A-I{slash}O-PadN6)") (class "Default")
      (node (ref "D16") (pin "N6") (pinfunction "I/O_N6") (pintype "bidirectional"))
    )
    (net (code "129") (name "unconnected-(D16A-I{slash}O-PadN7)") (class "Default")
      (node (ref "D16") (pin "N7") (pinfunction "I/O_N7") (pintype "bidirectional"))
    )
    (net (code "130") (name "unconnected-(D16A-I{slash}O-PadN8)") (class "Default")
      (node (ref "D16") (pin "N8") (pinfunction "I/O_N8") (pintype "bidirectional"))
    )
    (net (code "131") (name "unconnected-(D16A-I{slash}O-PadN9)") (class "Default")
      (node (ref "D16") (pin "N9") (pinfunction "I/O_N9") (pintype "bidirectional"))
    )
    (net (code "132") (name "unconnected-(D16A-I{slash}O-PadN10)") (class "Default")
      (node (ref "D16") (pin "N10") (pinfunction "I/O_N10") (pintype "bidirectional"))
    )
    (net (code "133") (name "unconnected-(D16A-I{slash}O-PadN11)") (class "Default")
      (node (ref "D16") (pin "N11") (pinfunction "I/O_N11") (pintype "bidirectional"))
    )
    (net (code "134") (name "unconnected-(D16A-I{slash}O-PadN13)") (class "Default")
      (node (ref "D16") (pin "N13") (pinfunction "I/O_N13") (pintype "bidirectional"))
    )
    (net (code "135") (name "unconnected-(D16A-I{slash}O-PadN14)") (class "Default")
      (node (ref "D16") (pin "N14") (pinfunction "I/O_N14") (pintype "bidirectional"))
    )
    (net (code "136") (name "unconnected-(D16A-I{slash}O-PadN15)") (class "Default")
      (node (ref "D16") (pin "N15") (pinfunction "I/O_N15") (pintype "bidirectional"))
    )
    (net (code "137") (name "unconnected-(D16A-I{slash}O-PadN16)") (class "Default")
      (node (ref "D16") (pin "N16") (pinfunction "I/O_N16") (pintype "bidirectional"))
    )
    (net (code "138") (name "unconnected-(D16A-I{slash}O-PadP4)") (class "Default")
      (node (ref "D16") (pin "P4") (pinfunction "I/O_P4") (pintype "bidirectional"))
    )
    (net (code "139") (name "unconnected-(D16A-I{slash}O-PadP6)") (class "Default")
      (node (ref "D16") (pin "P6") (pinfunction "I/O_P6") (pintype "bidirectional"))
    )
    (net (code "140") (name "unconnected-(D16A-I{slash}O-PadP7)") (class "Default")
      (node (ref "D16") (pin "P7") (pinfunction "I/O_P7") (pintype "bidirectional"))
    )
    (net (code "141") (name "unconnected-(D16A-I{slash}O-PadP8)") (class "Default")
      (node (ref "D16") (pin "P8") (pinfunction "I/O_P8") (pintype "bidirectional"))
    )
    (net (code "142") (name "unconnected-(D16A-I{slash}O-PadP10)") (class "Default")
      (node (ref "D16") (pin "P10") (pinfunction "I/O_P10") (pintype "bidirectional"))
    )
    (net (code "143") (name "unconnected-(D16A-I{slash}O-PadP13)") (class "Default")
      (node (ref "D16") (pin "P13") (pinfunction "I/O_P13") (pintype "bidirectional"))
    )
    (net (code "144") (name "unconnected-(D16A-I{slash}O-PadP14)") (class "Default")
      (node (ref "D16") (pin "P14") (pinfunction "I/O_P14") (pintype "bidirectional"))
    )
    (net (code "145") (name "unconnected-(D16A-I{slash}O-PadP15)") (class "Default")
      (node (ref "D16") (pin "P15") (pinfunction "I/O_P15") (pintype "bidirectional"))
    )
    (net (code "146") (name "unconnected-(D16A-I{slash}O-PadP16)") (class "Default")
      (node (ref "D16") (pin "P16") (pinfunction "I/O_P16") (pintype "bidirectional"))
    )
    (net (code "147") (name "unconnected-(D16A-I{slash}O-PadR3)") (class "Default")
      (node (ref "D16") (pin "R3") (pinfunction "I/O_R3") (pintype "bidirectional"))
    )
    (net (code "148") (name "unconnected-(D16A-I{slash}O-PadR5)") (class "Default")
      (node (ref "D16") (pin "R5") (pinfunction "I/O_R5") (pintype "bidirectional"))
    )
    (net (code "149") (name "unconnected-(D16A-I{slash}O-PadR6)") (class "Default")
      (node (ref "D16") (pin "R6") (pinfunction "I/O_R6") (pintype "bidirectional"))
    )
    (net (code "150") (name "unconnected-(D16A-I{slash}O-PadR7)") (class "Default")
      (node (ref "D16") (pin "R7") (pinfunction "I/O_R7") (pintype "bidirectional"))
    )
    (net (code "151") (name "unconnected-(D16A-I{slash}O-PadR8)") (class "Default")
      (node (ref "D16") (pin "R8") (pinfunction "I/O_R8") (pintype "bidirectional"))
    )
    (net (code "152") (name "unconnected-(D16A-I{slash}O-PadR9)") (class "Default")
      (node (ref "D16") (pin "R9") (pinfunction "I/O_R9") (pintype "bidirectional"))
    )
    (net (code "153") (name "unconnected-(D16A-I{slash}O-PadR10)") (class "Default")
      (node (ref "D16") (pin "R10") (pinfunction "I/O_R10") (pintype "bidirectional"))
    )
    (net (code "154") (name "unconnected-(D16A-I{slash}O-PadR12)") (class "Default")
      (node (ref "D16") (pin "R12") (pinfunction "I/O_R12") (pintype "bidirectional"))
    )
    (net (code "155") (name "unconnected-(D16A-I{slash}O-PadR13)") (class "Default")
      (node (ref "D16") (pin "R13") (pinfunction "I/O_R13") (pintype "bidirectional"))
    )
    (net (code "156") (name "unconnected-(D16A-I{slash}O-PadR14)") (class "Default")
      (node (ref "D16") (pin "R14") (pinfunction "I/O_R14") (pintype "bidirectional"))
    )
    (net (code "157") (name "unconnected-(D16A-I{slash}O-PadR15)") (class "Default")
      (node (ref "D16") (pin "R15") (pinfunction "I/O_R15") (pintype "bidirectional"))
    )
    (net (code "158") (name "unconnected-(D16A-I{slash}O-PadR16)") (class "Default")
      (node (ref "D16") (pin "R16") (pinfunction "I/O_R16") (pintype "bidirectional"))
    )
    (net (code "159") (name "unconnected-(D16A-I{slash}O-PadT5)") (class "Default")
      (node (ref "D16") (pin "T5") (pinfunction "I/O_T5") (pintype "bidirectional"))
    )
    (net (code "160") (name "unconnected-(D16A-I{slash}O-PadT7)") (class "Default")
      (node (ref "D16") (pin "T7") (pinfunction "I/O_T7") (pintype "bidirectional"))
    )
    (net (code "161") (name "unconnected-(D16A-I{slash}O-PadT8)") (class "Default")
      (node (ref "D16") (pin "T8") (pinfunction "I/O_T8") (pintype "bidirectional"))
    )
    (net (code "162") (name "unconnected-(D16A-I{slash}O-PadT10)") (class "Default")
      (node (ref "D16") (pin "T10") (pinfunction "I/O_T10") (pintype "bidirectional"))
    )
    (net (code "163") (name "unconnected-(D16A-I{slash}O-PadT15)") (class "Default")
      (node (ref "D16") (pin "T15") (pinfunction "I/O_T15") (pintype "bidirectional"))
    )
    (net (code "164") (name "unconnected-(D16A-I{slash}O-PadT16)") (class "Default")
      (node (ref "D16") (pin "T16") (pinfunction "I/O_T16") (pintype "bidirectional"))
    )
    (net (code "165") (name "unconnected-(D16B-I{slash}O,GSR-PadC4)") (class "Default")
      (node (ref "D16") (pin "C4") (pinfunction "I/O,GSR_C4") (pintype "bidirectional"))
    )
    (net (code "166") (name "unconnected-(D16B-I{slash}O,GTS0-PadD4)") (class "Default")
      (node (ref "D16") (pin "D4") (pinfunction "I/O,GTS0_D4") (pintype "bidirectional"))
    )
    (net (code "167") (name "unconnected-(D16B-I{slash}O,GTS1-PadE5)") (class "Default")
      (node (ref "D16") (pin "E5") (pinfunction "I/O,GTS1_E5") (pintype "bidirectional"))
    )
    (net (code "168") (name "unconnected-(D16B-I{slash}O,GTS2-PadD3)") (class "Default")
      (node (ref "D16") (pin "D3") (pinfunction "I/O,GTS2_D3") (pintype "bidirectional"))
    )
    (net (code "169") (name "unconnected-(D16B-I{slash}O,GTS3-PadE3)") (class "Default")
      (node (ref "D16") (pin "E3") (pinfunction "I/O,GTS3_E3") (pintype "bidirectional"))
    )
    (net (code "170") (name "unconnected-(D16B-I{slash}O-PadA2)") (class "Default")
      (node (ref "D16") (pin "A2") (pinfunction "I/O_A2") (pintype "bidirectional"))
    )
    (net (code "171") (name "unconnected-(D16B-I{slash}O-PadA3)") (class "Default")
      (node (ref "D16") (pin "A3") (pinfunction "I/O_A3") (pintype "bidirectional"))
    )
    (net (code "172") (name "unconnected-(D16B-I{slash}O-PadA4)") (class "Default")
      (node (ref "D16") (pin "A4") (pinfunction "I/O_A4") (pintype "bidirectional"))
    )
    (net (code "173") (name "unconnected-(D16B-I{slash}O-PadA5)") (class "Default")
      (node (ref "D16") (pin "A5") (pinfunction "I/O_A5") (pintype "bidirectional"))
    )
    (net (code "174") (name "unconnected-(D16B-I{slash}O-PadA6)") (class "Default")
      (node (ref "D16") (pin "A6") (pinfunction "I/O_A6") (pintype "bidirectional"))
    )
    (net (code "175") (name "unconnected-(D16B-I{slash}O-PadA7)") (class "Default")
      (node (ref "D16") (pin "A7") (pinfunction "I/O_A7") (pintype "bidirectional"))
    )
    (net (code "176") (name "unconnected-(D16B-I{slash}O-PadA9)") (class "Default")
      (node (ref "D16") (pin "A9") (pinfunction "I/O_A9") (pintype "bidirectional"))
    )
    (net (code "177") (name "unconnected-(D16B-I{slash}O-PadA13)") (class "Default")
      (node (ref "D16") (pin "A13") (pinfunction "I/O_A13") (pintype "bidirectional"))
    )
    (net (code "178") (name "unconnected-(D16B-I{slash}O-PadA14)") (class "Default")
      (node (ref "D16") (pin "A14") (pinfunction "I/O_A14") (pintype "bidirectional"))
    )
    (net (code "179") (name "unconnected-(D16B-I{slash}O-PadB3)") (class "Default")
      (node (ref "D16") (pin "B3") (pinfunction "I/O_B3") (pintype "bidirectional"))
    )
    (net (code "180") (name "unconnected-(D16B-I{slash}O-PadB4)") (class "Default")
      (node (ref "D16") (pin "B4") (pinfunction "I/O_B4") (pintype "bidirectional"))
    )
    (net (code "181") (name "unconnected-(D16B-I{slash}O-PadB5)") (class "Default")
      (node (ref "D16") (pin "B5") (pinfunction "I/O_B5") (pintype "bidirectional"))
    )
    (net (code "182") (name "unconnected-(D16B-I{slash}O-PadB9)") (class "Default")
      (node (ref "D16") (pin "B9") (pinfunction "I/O_B9") (pintype "bidirectional"))
    )
    (net (code "183") (name "unconnected-(D16B-I{slash}O-PadB10)") (class "Default")
      (node (ref "D16") (pin "B10") (pinfunction "I/O_B10") (pintype "bidirectional"))
    )
    (net (code "184") (name "unconnected-(D16B-I{slash}O-PadB13)") (class "Default")
      (node (ref "D16") (pin "B13") (pinfunction "I/O_B13") (pintype "bidirectional"))
    )
    (net (code "185") (name "unconnected-(D16B-I{slash}O-PadC3)") (class "Default")
      (node (ref "D16") (pin "C3") (pinfunction "I/O_C3") (pintype "bidirectional"))
    )
    (net (code "186") (name "unconnected-(D16B-I{slash}O-PadC7)") (class "Default")
      (node (ref "D16") (pin "C7") (pinfunction "I/O_C7") (pintype "bidirectional"))
    )
    (net (code "187") (name "unconnected-(D16B-I{slash}O-PadC8)") (class "Default")
      (node (ref "D16") (pin "C8") (pinfunction "I/O_C8") (pintype "bidirectional"))
    )
    (net (code "188") (name "unconnected-(D16B-I{slash}O-PadC9)") (class "Default")
      (node (ref "D16") (pin "C9") (pinfunction "I/O_C9") (pintype "bidirectional"))
    )
    (net (code "189") (name "unconnected-(D16B-I{slash}O-PadC10)") (class "Default")
      (node (ref "D16") (pin "C10") (pinfunction "I/O_C10") (pintype "bidirectional"))
    )
    (net (code "190") (name "unconnected-(D16B-I{slash}O-PadC11)") (class "Default")
      (node (ref "D16") (pin "C11") (pinfunction "I/O_C11") (pintype "bidirectional"))
    )
    (net (code "191") (name "unconnected-(D16B-I{slash}O-PadC12)") (class "Default")
      (node (ref "D16") (pin "C12") (pinfunction "I/O_C12") (pintype "bidirectional"))
    )
    (net (code "192") (name "unconnected-(D16B-I{slash}O-PadC13)") (class "Default")
      (node (ref "D16") (pin "C13") (pinfunction "I/O_C13") (pintype "bidirectional"))
    )
    (net (code "193") (name "unconnected-(D16B-I{slash}O-PadC14)") (class "Default")
      (node (ref "D16") (pin "C14") (pinfunction "I/O_C14") (pintype "bidirectional"))
    )
    (net (code "194") (name "unconnected-(D16B-I{slash}O-PadD7)") (class "Default")
      (node (ref "D16") (pin "D7") (pinfunction "I/O_D7") (pintype "bidirectional"))
    )
    (net (code "195") (name "unconnected-(D16B-I{slash}O-PadD8)") (class "Default")
      (node (ref "D16") (pin "D8") (pinfunction "I/O_D8") (pintype "bidirectional"))
    )
    (net (code "196") (name "unconnected-(D16B-I{slash}O-PadD9)") (class "Default")
      (node (ref "D16") (pin "D9") (pinfunction "I/O_D9") (pintype "bidirectional"))
    )
    (net (code "197") (name "unconnected-(D16B-I{slash}O-PadD10)") (class "Default")
      (node (ref "D16") (pin "D10") (pinfunction "I/O_D10") (pintype "bidirectional"))
    )
    (net (code "198") (name "unconnected-(D16B-I{slash}O-PadD11)") (class "Default")
      (node (ref "D16") (pin "D11") (pinfunction "I/O_D11") (pintype "bidirectional"))
    )
    (net (code "199") (name "unconnected-(D16B-I{slash}O-PadD13)") (class "Default")
      (node (ref "D16") (pin "D13") (pinfunction "I/O_D13") (pintype "bidirectional"))
    )
    (net (code "200") (name "unconnected-(D16B-I{slash}O-PadD15)") (class "Default")
      (node (ref "D16") (pin "D15") (pinfunction "I/O_D15") (pintype "bidirectional"))
    )
    (net (code "201") (name "unconnected-(D16B-I{slash}O-PadE4)") (class "Default")
      (node (ref "D16") (pin "E4") (pinfunction "I/O_E4") (pintype "bidirectional"))
    )
    (net (code "202") (name "unconnected-(D16B-I{slash}O-PadE8)") (class "Default")
      (node (ref "D16") (pin "E8") (pinfunction "I/O_E8") (pintype "bidirectional"))
    )
    (net (code "203") (name "unconnected-(D16B-I{slash}O-PadE9)") (class "Default")
      (node (ref "D16") (pin "E9") (pinfunction "I/O_E9") (pintype "bidirectional"))
    )
    (net (code "204") (name "unconnected-(D16B-I{slash}O-PadE10)") (class "Default")
      (node (ref "D16") (pin "E10") (pinfunction "I/O_E10") (pintype "bidirectional"))
    )
    (net (code "205") (name "unconnected-(D16B-I{slash}O-PadE11)") (class "Default")
      (node (ref "D16") (pin "E11") (pinfunction "I/O_E11") (pintype "bidirectional"))
    )
    (net (code "206") (name "unconnected-(D16B-I{slash}O-PadE12)") (class "Default")
      (node (ref "D16") (pin "E12") (pinfunction "I/O_E12") (pintype "bidirectional"))
    )
    (net (code "207") (name "unconnected-(D16B-I{slash}O-PadE13)") (class "Default")
      (node (ref "D16") (pin "E13") (pinfunction "I/O_E13") (pintype "bidirectional"))
    )
    (net (code "208") (name "unconnected-(D16B-I{slash}O-PadE14)") (class "Default")
      (node (ref "D16") (pin "E14") (pinfunction "I/O_E14") (pintype "bidirectional"))
    )
    (net (code "209") (name "unconnected-(D16B-I{slash}O-PadE15)") (class "Default")
      (node (ref "D16") (pin "E15") (pinfunction "I/O_E15") (pintype "bidirectional"))
    )
    (net (code "210") (name "unconnected-(D16B-I{slash}O-PadE16)") (class "Default")
      (node (ref "D16") (pin "E16") (pinfunction "I/O_E16") (pintype "bidirectional"))
    )
    (net (code "211") (name "unconnected-(D16B-I{slash}O-PadF5)") (class "Default")
      (node (ref "D16") (pin "F5") (pinfunction "I/O_F5") (pintype "bidirectional"))
    )
    (net (code "212") (name "unconnected-(D16B-I{slash}O-PadF12)") (class "Default")
      (node (ref "D16") (pin "F12") (pinfunction "I/O_F12") (pintype "bidirectional"))
    )
    (net (code "213") (name "unconnected-(D16B-I{slash}O-PadF13)") (class "Default")
      (node (ref "D16") (pin "F13") (pinfunction "I/O_F13") (pintype "bidirectional"))
    )
    (net (code "214") (name "unconnected-(D16B-I{slash}O-PadF14)") (class "Default")
      (node (ref "D16") (pin "F14") (pinfunction "I/O_F14") (pintype "bidirectional"))
    )
    (net (code "215") (name "unconnected-(D16B-I{slash}O-PadF15)") (class "Default")
      (node (ref "D16") (pin "F15") (pinfunction "I/O_F15") (pintype "bidirectional"))
    )
    (net (code "216") (name "unconnected-(D16B-I{slash}O-PadF16)") (class "Default")
      (node (ref "D16") (pin "F16") (pinfunction "I/O_F16") (pintype "bidirectional"))
    )
    (net (code "217") (name "unconnected-(D16B-I{slash}O-PadG4)") (class "Default")
      (node (ref "D16") (pin "G4") (pinfunction "I/O_G4") (pintype "bidirectional"))
    )
    (net (code "218") (name "unconnected-(D16B-I{slash}O-PadG5)") (class "Default")
      (node (ref "D16") (pin "G5") (pinfunction "I/O_G5") (pintype "bidirectional"))
    )
    (net (code "219") (name "unconnected-(D16B-I{slash}O-PadG11)") (class "Default")
      (node (ref "D16") (pin "G11") (pinfunction "I/O_G11") (pintype "bidirectional"))
    )
    (net (code "220") (name "unconnected-(D16B-I{slash}O-PadG13)") (class "Default")
      (node (ref "D16") (pin "G13") (pinfunction "I/O_G13") (pintype "bidirectional"))
    )
    (net (code "221") (name "unconnected-(D16B-I{slash}O-PadG14)") (class "Default")
      (node (ref "D16") (pin "G14") (pinfunction "I/O_G14") (pintype "bidirectional"))
    )
    (net (code "222") (name "unconnected-(D16B-I{slash}O-PadG15)") (class "Default")
      (node (ref "D16") (pin "G15") (pinfunction "I/O_G15") (pintype "bidirectional"))
    )
    (net (code "223") (name "unconnected-(D16B-I{slash}O-PadG16)") (class "Default")
      (node (ref "D16") (pin "G16") (pinfunction "I/O_G16") (pintype "bidirectional"))
    )
    (net (code "224") (name "unconnected-(D16B-I{slash}O-PadH3)") (class "Default")
      (node (ref "D16") (pin "H3") (pinfunction "I/O_H3") (pintype "bidirectional"))
    )
    (net (code "225") (name "unconnected-(D16B-I{slash}O-PadH4)") (class "Default")
      (node (ref "D16") (pin "H4") (pinfunction "I/O_H4") (pintype "bidirectional"))
    )
    (net (code "226") (name "unconnected-(D16B-I{slash}O-PadH5)") (class "Default")
      (node (ref "D16") (pin "H5") (pinfunction "I/O_H5") (pintype "bidirectional"))
    )
    (net (code "227") (name "unconnected-(D16B-I{slash}O-PadH12)") (class "Default")
      (node (ref "D16") (pin "H12") (pinfunction "I/O_H12") (pintype "bidirectional"))
    )
    (net (code "228") (name "unconnected-(D16B-I{slash}O-PadH13)") (class "Default")
      (node (ref "D16") (pin "H13") (pinfunction "I/O_H13") (pintype "bidirectional"))
    )
    (net (code "229") (name "unconnected-(D16B-I{slash}O-PadH14)") (class "Default")
      (node (ref "D16") (pin "H14") (pinfunction "I/O_H14") (pintype "bidirectional"))
    )
    (net (code "230") (name "unconnected-(D16B-I{slash}O-PadH15)") (class "Default")
      (node (ref "D16") (pin "H15") (pinfunction "I/O_H15") (pintype "bidirectional"))
    )
    (net (code "231") (name "unconnected-(D16B-I{slash}O-PadH16)") (class "Default")
      (node (ref "D16") (pin "H16") (pinfunction "I/O_H16") (pintype "bidirectional"))
    )
    (net (code "232") (name "unconnected-(D16B-I{slash}O-PadJ12)") (class "Default")
      (node (ref "D16") (pin "J12") (pinfunction "I/O_J12") (pintype "bidirectional"))
    )
    (net (code "233") (name "unconnected-(D16F-NC-PadA1)") (class "Default")
      (node (ref "D16") (pin "A1") (pinfunction "NC_A1") (pintype "passive+no_connect"))
    )
    (net (code "234") (name "unconnected-(D16F-NC-PadC2)") (class "Default")
      (node (ref "D16") (pin "C2") (pinfunction "NC_C2") (pintype "passive+no_connect"))
    )
    (net (code "235") (name "unconnected-(D16F-NC-PadC5)") (class "Default")
      (node (ref "D16") (pin "C5") (pinfunction "NC_C5") (pintype "passive+no_connect"))
    )
    (net (code "236") (name "unconnected-(D16F-NC-PadC6)") (class "Default")
      (node (ref "D16") (pin "C6") (pinfunction "NC_C6") (pintype "passive+no_connect"))
    )
    (net (code "237") (name "unconnected-(D16F-NC-PadC15)") (class "Default")
      (node (ref "D16") (pin "C15") (pinfunction "NC_C15") (pintype "passive+no_connect"))
    )
    (net (code "238") (name "unconnected-(D16F-NC-PadD1)") (class "Default")
      (node (ref "D16") (pin "D1") (pinfunction "NC_D1") (pintype "passive+no_connect"))
    )
    (net (code "239") (name "unconnected-(D16F-NC-PadD6)") (class "Default")
      (node (ref "D16") (pin "D6") (pinfunction "NC_D6") (pintype "passive+no_connect"))
    )
    (net (code "240") (name "unconnected-(D16F-NC-PadD14)") (class "Default")
      (node (ref "D16") (pin "D14") (pinfunction "NC_D14") (pintype "passive+no_connect"))
    )
    (net (code "241") (name "unconnected-(D16F-NC-PadD16)") (class "Default")
      (node (ref "D16") (pin "D16") (pinfunction "NC_D16") (pintype "passive+no_connect"))
    )
    (net (code "242") (name "unconnected-(D16F-NC-PadE1)") (class "Default")
      (node (ref "D16") (pin "E1") (pinfunction "NC_E1") (pintype "passive+no_connect"))
    )
    (net (code "243") (name "unconnected-(D16F-NC-PadE6)") (class "Default")
      (node (ref "D16") (pin "E6") (pinfunction "NC_E6") (pintype "passive+no_connect"))
    )
    (net (code "244") (name "unconnected-(D16F-NC-PadE7)") (class "Default")
      (node (ref "D16") (pin "E7") (pinfunction "NC_E7") (pintype "passive+no_connect"))
    )
    (net (code "245") (name "unconnected-(D16F-NC-PadF1)") (class "Default")
      (node (ref "D16") (pin "F1") (pinfunction "NC_F1") (pintype "passive+no_connect"))
    )
    (net (code "246") (name "unconnected-(D16F-NC-PadG1)") (class "Default")
      (node (ref "D16") (pin "G1") (pinfunction "NC_G1") (pintype "passive+no_connect"))
    )
    (net (code "247") (name "unconnected-(D16F-NC-PadG2)") (class "Default")
      (node (ref "D16") (pin "G2") (pinfunction "NC_G2") (pintype "passive+no_connect"))
    )
    (net (code "248") (name "unconnected-(D16F-NC-PadG12)") (class "Default")
      (node (ref "D16") (pin "G12") (pinfunction "NC_G12") (pintype "passive+no_connect"))
    )
    (net (code "249") (name "unconnected-(D16F-NC-PadJ16)") (class "Default")
      (node (ref "D16") (pin "J16") (pinfunction "NC_J16") (pintype "passive+no_connect"))
    )
    (net (code "250") (name "unconnected-(D16F-NC-PadK12)") (class "Default")
      (node (ref "D16") (pin "K12") (pinfunction "NC_K12") (pintype "passive+no_connect"))
    )
    (net (code "251") (name "unconnected-(D16F-NC-PadM4)") (class "Default")
      (node (ref "D16") (pin "M4") (pinfunction "NC_M4") (pintype "passive+no_connect"))
    )
    (net (code "252") (name "unconnected-(D16F-NC-PadM9)") (class "Default")
      (node (ref "D16") (pin "M9") (pinfunction "NC_M9") (pintype "passive+no_connect"))
    )
    (net (code "253") (name "unconnected-(D16F-NC-PadM10)") (class "Default")
      (node (ref "D16") (pin "M10") (pinfunction "NC_M10") (pintype "passive+no_connect"))
    )
    (net (code "254") (name "unconnected-(D16F-NC-PadP9)") (class "Default")
      (node (ref "D16") (pin "P9") (pinfunction "NC_P9") (pintype "passive+no_connect"))
    )
    (net (code "255") (name "unconnected-(D16F-NC-PadP11)") (class "Default")
      (node (ref "D16") (pin "P11") (pinfunction "NC_P11") (pintype "passive+no_connect"))
    )
    (net (code "256") (name "unconnected-(D16F-NC-PadT9)") (class "Default")
      (node (ref "D16") (pin "T9") (pinfunction "NC_T9") (pintype "passive+no_connect"))
    )
    (net (code "257") (name "unconnected-(D16F-NC-PadT11)") (class "Default")
      (node (ref "D16") (pin "T11") (pinfunction "NC_T11") (pintype "passive+no_connect"))
    )
    (net (code "258") (name "unconnected-(D16F-NC-PadT12)") (class "Default")
      (node (ref "D16") (pin "T12") (pinfunction "NC_T12") (pintype "passive+no_connect"))
    )
    (net (code "259") (name "unconnected-(D16F-NC-PadT13)") (class "Default")
      (node (ref "D16") (pin "T13") (pinfunction "NC_T13") (pintype "passive+no_connect"))
    )
    (net (code "260") (name "unconnected-(D16F-NC-PadT14)") (class "Default")
      (node (ref "D16") (pin "T14") (pinfunction "NC_T14") (pintype "passive+no_connect"))
    )
    (net (code "261") (name "unconnected-(R80-Pad1)") (class "Default")
      (node (ref "R80") (pin "1") (pinfunction "1_1") (pintype "passive"))
    )
    (net (code "262") (name "unconnected-(R80-Pad8)") (class "Default")
      (node (ref "R80") (pin "8") (pinfunction "8_8") (pintype "passive"))
    )
    (net (code "263") (name "unconnected-(R89-Pad4)") (class "Default")
      (node (ref "R89") (pin "4") (pinfunction "4_4") (pintype "passive"))
    )
    (net (code "264") (name "unconnected-(R89-Pad5)") (class "Default")
      (node (ref "R89") (pin "5") (pinfunction "5_5") (pintype "passive"))
    )
    (net (code "265") (name "unconnected-(R91-Pad1)") (class "Default")
      (node (ref "R91") (pin "1") (pinfunction "1_1") (pintype "passive"))
    )
    (net (code "266") (name "unconnected-(R91-Pad8)") (class "Default")
      (node (ref "R91") (pin "8") (pinfunction "8_8") (pintype "passive"))
    )
    (net (code "267") (name "unconnected-(X3-Pad12)") (class "Default")
      (node (ref "X3") (pin "12") (pinfunction "12_12") (pintype "passive+no_connect"))
    )
    (net (code "268") (name "unconnected-(X3-Pad14)") (class "Default")
      (node (ref "X3") (pin "14") (pinfunction "14_14") (pintype "passive+no_connect"))
    )
  )
)
